# Connectors.net
KiCad netlist of a schematic drawn in Altium Designer
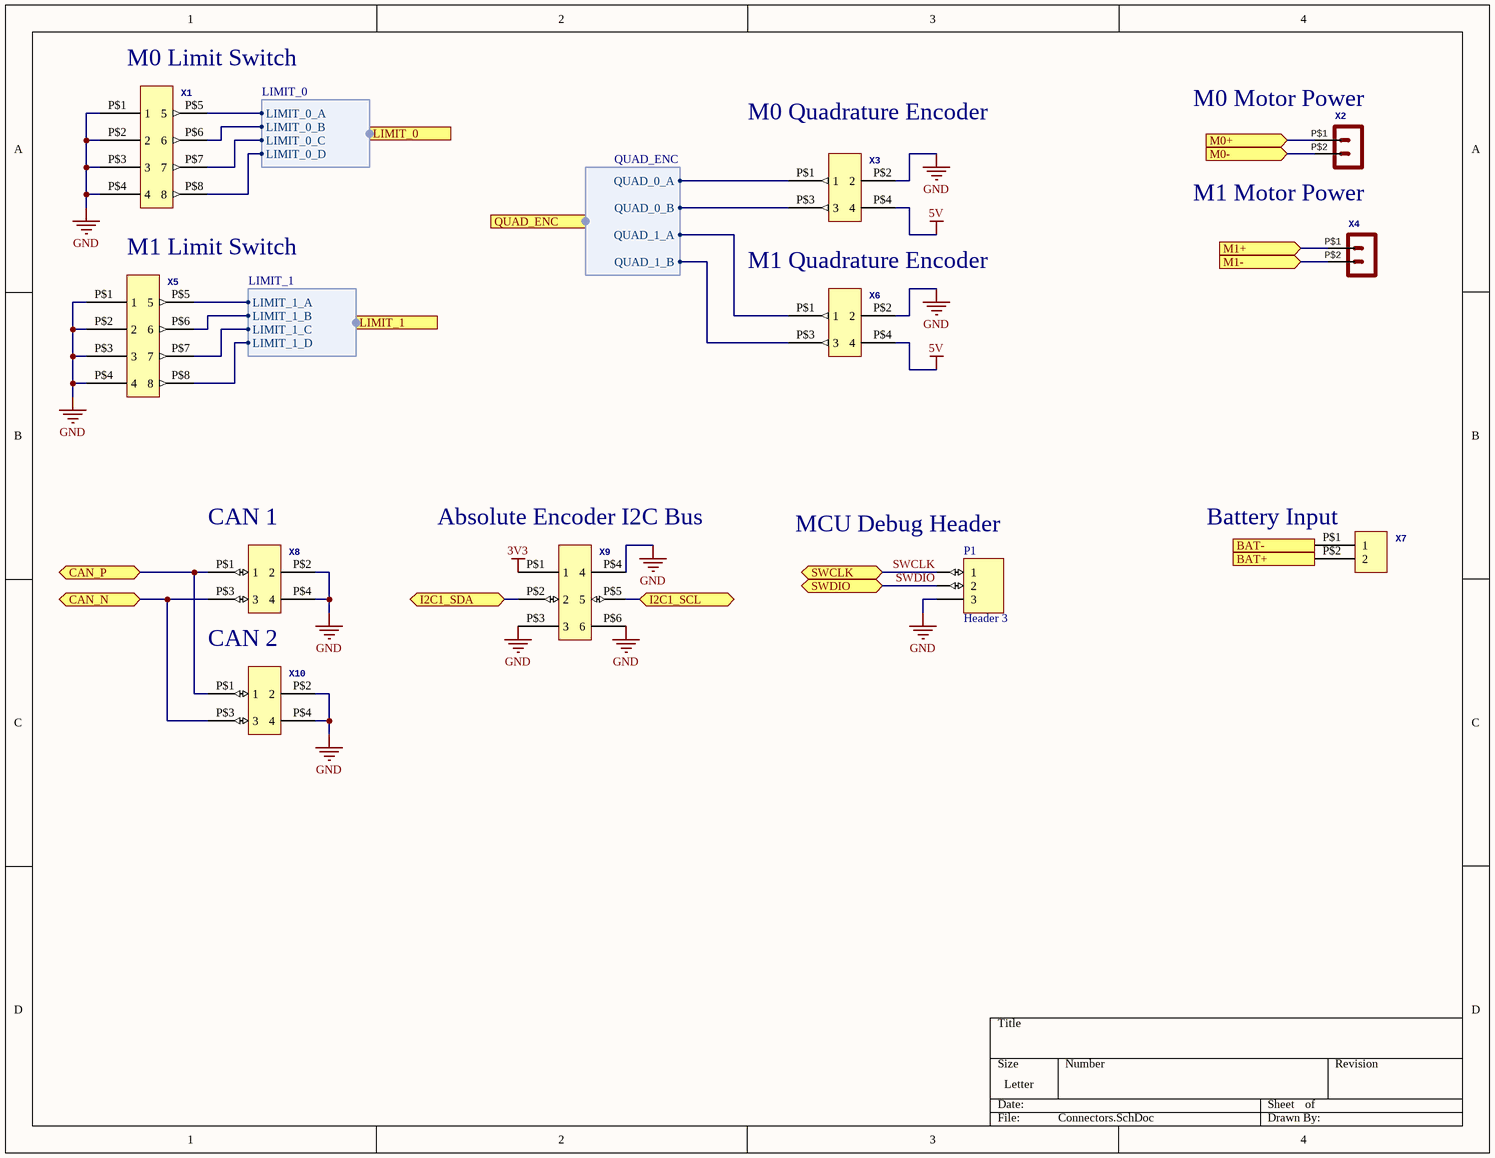
[diagram p0: Connectors.SchDoc]

(export (version "E")
  (design (tool "Eeschema 10.0.6"))
  (components
    (comp (ref "P1")
      (value "Header 3")
      (footprint "HDR1X3")
      (description "Header, 3-Pin")
      (fields (field (name "PUBLISHER") "Altium Limited"))
      (libsource (lib "Miscellaneous Connectors") (part "Header 3"))
    )
    (comp (ref "X1")
      (value "Molex 43045-0812")
      (footprint "43045-0812")
      (libsource (lib "Molex Microfit") (part "Micro-Fit Molex 8 Pin 2 Row Vertical"))
    )
    (comp (ref "X2")
      (value "Molex - Micro-Fit 3.0 Series connector,  3.00mm (0.118\") pitch header, 2 positions.")
      (footprint "Molex MicroFit:43045-0212")
      (libsource (lib "Molex Microfit") (part "HEADER_POS2_?43045-0212"))
    )
    (comp (ref "X3")
      (value "Molex 43045-0412")
      (footprint "43045-0412")
      (libsource (lib "Molex Microfit") (part "Micro-Fit Molex 4 Pin 2 Row Vertical"))
    )
    (comp (ref "X4")
      (value "Molex - Micro-Fit 3.0 Series connector,  3.00mm (0.118\") pitch header, 2 positions.")
      (footprint "Molex MicroFit:43045-0212")
      (libsource (lib "Molex Microfit") (part "HEADER_POS2_?43045-0212"))
    )
    (comp (ref "X5")
      (value "Molex 43045-0812")
      (footprint "43045-0812")
      (libsource (lib "Molex Microfit") (part "Micro-Fit Molex 8 Pin 2 Row Vertical"))
    )
    (comp (ref "X6")
      (value "Molex 43045-0412")
      (footprint "43045-0412")
      (libsource (lib "Molex Microfit") (part "Micro-Fit Molex 4 Pin 2 Row Vertical"))
    )
    (comp (ref "X7")
      (value "Molex 43650-0215")
      (footprint "43650-0215")
      (libsource (lib "Molex Microfit") (part "Micro-Fit Molex 2 Pin Vertical"))
    )
    (comp (ref "X8")
      (value "Molex 43045-0412")
      (footprint "43045-0412")
      (libsource (lib "Molex Microfit") (part "Micro-Fit Molex 4 Pin 2 Row Vertical"))
    )
    (comp (ref "X9")
      (value "Molex 43045-0612")
      (footprint "Molex MicroFit:43045-0612")
      (libsource (lib "Molex Microfit") (part "Micro-Fit Molex 6 Pin 2 Row Vertical"))
    )
    (comp (ref "X10")
      (value "Molex 43045-0412")
      (footprint "43045-0412")
      (libsource (lib "Molex Microfit") (part "Micro-Fit Molex 4 Pin 2 Row Vertical"))
    )
  )
  (nets
    (net (code "4") (name "/BAT+") (class "Default")
      (node (ref "X7") (pin "P$2") (pinfunction "2_P$2") (pintype "passive"))
    )
    (net (code "5") (name "/BAT-") (class "Default")
      (node (ref "X7") (pin "P$1") (pinfunction "1_P$1") (pintype "passive"))
    )
    (net (code "6") (name "/CAN_N") (class "Default")
      (node (ref "X10") (pin "P$3") (pinfunction "3_P$3") (pintype "output"))
      (node (ref "X8") (pin "P$3") (pinfunction "3_P$3") (pintype "output"))
    )
    (net (code "7") (name "/CAN_P") (class "Default")
      (node (ref "X10") (pin "P$1") (pinfunction "1_P$1") (pintype "output"))
      (node (ref "X8") (pin "P$1") (pinfunction "1_P$1") (pintype "output"))
    )
    (net (code "8") (name "/I2C1_SCL") (class "Default")
      (node (ref "X9") (pin "P$5") (pinfunction "5_P$5") (pintype "bidirectional"))
    )
    (net (code "9") (name "/I2C1_SDA") (class "Default")
      (node (ref "X9") (pin "P$2") (pinfunction "2_P$2") (pintype "bidirectional"))
    )
    (net (code "10") (name "/LIMIT_0_A") (class "Default")
      (node (ref "X1") (pin "P$5") (pinfunction "5_P$5") (pintype "output"))
    )
    (net (code "11") (name "/LIMIT_0_B") (class "Default")
      (node (ref "X1") (pin "P$6") (pinfunction "6_P$6") (pintype "output"))
    )
    (net (code "12") (name "/LIMIT_0_C") (class "Default")
      (node (ref "X1") (pin "P$7") (pinfunction "7_P$7") (pintype "output"))
    )
    (net (code "13") (name "/LIMIT_0_D") (class "Default")
      (node (ref "X1") (pin "P$8") (pinfunction "8_P$8") (pintype "output"))
    )
    (net (code "14") (name "/LIMIT_1_A") (class "Default")
      (node (ref "X5") (pin "P$5") (pinfunction "5_P$5") (pintype "output"))
    )
    (net (code "15") (name "/LIMIT_1_B") (class "Default")
      (node (ref "X5") (pin "P$6") (pinfunction "6_P$6") (pintype "output"))
    )
    (net (code "16") (name "/LIMIT_1_C") (class "Default")
      (node (ref "X5") (pin "P$7") (pinfunction "7_P$7") (pintype "output"))
    )
    (net (code "17") (name "/LIMIT_1_D") (class "Default")
      (node (ref "X5") (pin "P$8") (pinfunction "8_P$8") (pintype "output"))
    )
    (net (code "18") (name "/M0+") (class "Default")
      (node (ref "X2") (pin "P$1") (pinfunction "1_P$1") (pintype "passive"))
    )
    (net (code "19") (name "/M0-") (class "Default")
      (node (ref "X2") (pin "P$2") (pinfunction "2_P$2") (pintype "passive"))
    )
    (net (code "20") (name "/M1+") (class "Default")
      (node (ref "X4") (pin "P$1") (pinfunction "1_P$1") (pintype "passive"))
    )
    (net (code "21") (name "/M1-") (class "Default")
      (node (ref "X4") (pin "P$2") (pinfunction "2_P$2") (pintype "passive"))
    )
    (net (code "22") (name "/QUAD_0_A") (class "Default")
      (node (ref "X3") (pin "P$1") (pinfunction "1_P$1") (pintype "output"))
    )
    (net (code "23") (name "/QUAD_0_B") (class "Default")
      (node (ref "X3") (pin "P$3") (pinfunction "3_P$3") (pintype "output"))
    )
    (net (code "24") (name "/QUAD_1_A") (class "Default")
      (node (ref "X6") (pin "P$1") (pinfunction "1_P$1") (pintype "output"))
    )
    (net (code "25") (name "/QUAD_1_B") (class "Default")
      (node (ref "X6") (pin "P$3") (pinfunction "3_P$3") (pintype "output"))
    )
    (net (code "26") (name "/SWCLK") (class "Default")
      (node (ref "P1") (pin "1") (pinfunction "1_1") (pintype "bidirectional"))
    )
    (net (code "27") (name "/SWDIO") (class "Default")
      (node (ref "P1") (pin "2") (pinfunction "2_2") (pintype "bidirectional"))
    )
    (net (code "31") (name "3V3") (class "Default")
      (node (ref "X9") (pin "P$1") (pinfunction "1_P$1") (pintype "passive"))
    )
    (net (code "32") (name "5V") (class "Default")
      (node (ref "X3") (pin "P$4") (pinfunction "4_P$4") (pintype "passive"))
      (node (ref "X6") (pin "P$4") (pinfunction "4_P$4") (pintype "passive"))
    )
    (net (code "33") (name "GND") (class "Default")
      (node (ref "P1") (pin "3") (pinfunction "3_3") (pintype "passive"))
      (node (ref "X1") (pin "P$1") (pinfunction "1_P$1") (pintype "passive"))
      (node (ref "X1") (pin "P$2") (pinfunction "2_P$2") (pintype "passive"))
      (node (ref "X1") (pin "P$3") (pinfunction "3_P$3") (pintype "passive"))
      (node (ref "X1") (pin "P$4") (pinfunction "4_P$4") (pintype "passive"))
      (node (ref "X10") (pin "P$2") (pinfunction "2_P$2") (pintype "passive"))
      (node (ref "X10") (pin "P$4") (pinfunction "4_P$4") (pintype "passive"))
      (node (ref "X3") (pin "P$2") (pinfunction "2_P$2") (pintype "passive"))
      (node (ref "X5") (pin "P$1") (pinfunction "1_P$1") (pintype "passive"))
      (node (ref "X5") (pin "P$2") (pinfunction "2_P$2") (pintype "passive"))
      (node (ref "X5") (pin "P$3") (pinfunction "3_P$3") (pintype "passive"))
      (node (ref "X5") (pin "P$4") (pinfunction "4_P$4") (pintype "passive"))
      (node (ref "X6") (pin "P$2") (pinfunction "2_P$2") (pintype "passive"))
      (node (ref "X8") (pin "P$2") (pinfunction "2_P$2") (pintype "passive"))
      (node (ref "X8") (pin "P$4") (pinfunction "4_P$4") (pintype "passive"))
      (node (ref "X9") (pin "P$3") (pinfunction "3_P$3") (pintype "passive"))
      (node (ref "X9") (pin "P$4") (pinfunction "4_P$4") (pintype "passive"))
      (node (ref "X9") (pin "P$6") (pinfunction "6_P$6") (pintype "passive"))
    )
  )
)
